# OpenHPI_Embedded_Smart_Home_RPi_Board2.net
KiCad netlist of a schematic drawn in EAGLE
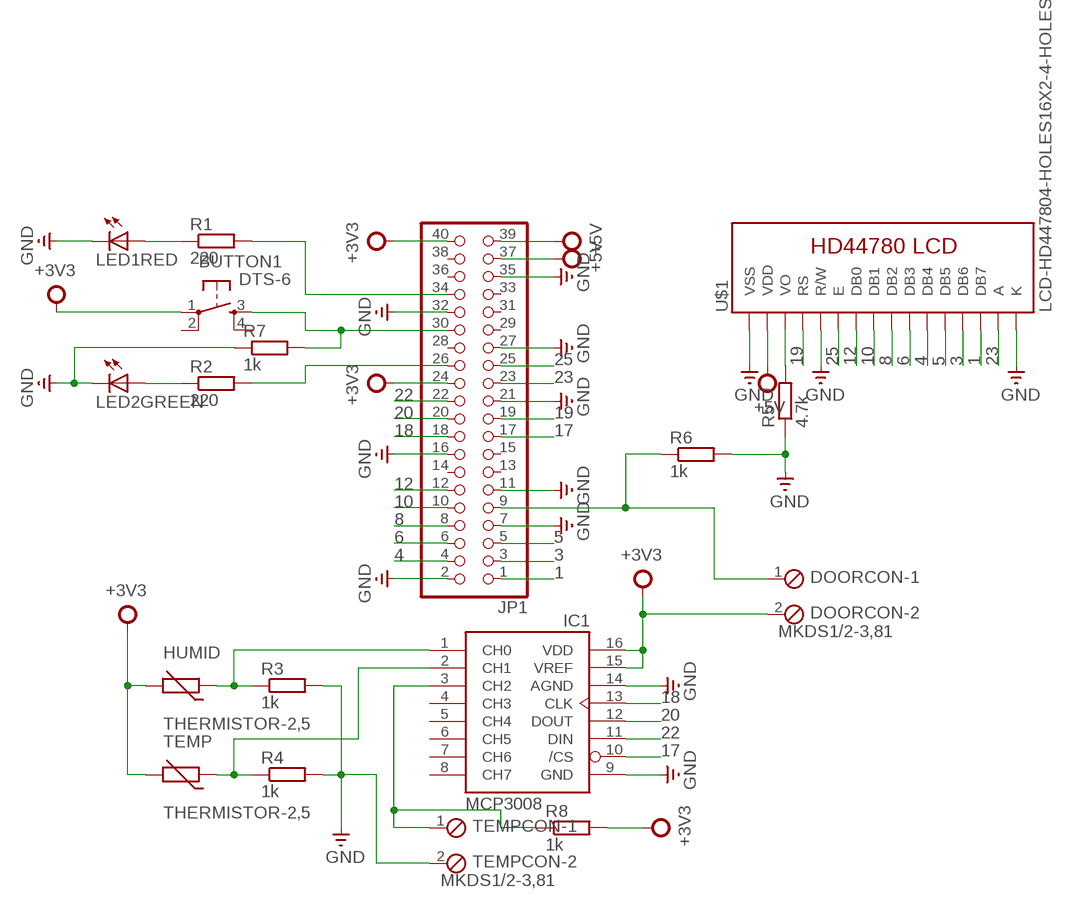
[diagram p0: schematic, sheet 1]

(export (version "E")
  (design (tool "Eeschema 10.0.6"))
  (components
    (comp (ref "BUTTON1")
      (value "DTS-6")
      (footprint "eagle-import:DTS-6")
      (libsource (lib "eagle-import") (part "DTS-6"))
    )
    (comp (ref "DOORCON")
      (value "MKDS1/2-3,81")
      (footprint "eagle-import:2POL381")
      (libsource (lib "eagle-import") (part "MKDS1/2-3,81"))
    )
    (comp (ref "HUMID")
      (value "THERMISTOR-2,5")
      (footprint "eagle-import:RS-2,5")
      (libsource (lib "eagle-import") (part "THERMISTOR-2,5"))
    )
    (comp (ref "IC1")
      (value "MCP3008")
      (footprint "eagle-import:DIL16")
      (libsource (lib "eagle-import") (part "MCP3008"))
    )
    (comp (ref "JP1")
      (value "PINHD-2X20")
      (footprint "eagle-import:2X20")
      (libsource (lib "eagle-import") (part "PINHD-2X20"))
    )
    (comp (ref "LED1RED")
      (value "LED5MM")
      (footprint "eagle-import:LED5MM")
      (libsource (lib "eagle-import") (part "LED5MM"))
    )
    (comp (ref "LED2GREEN")
      (value "LED5MM")
      (footprint "eagle-import:LED5MM")
      (libsource (lib "eagle-import") (part "LED5MM"))
    )
    (comp (ref "R1")
      (value "220")
      (footprint "eagle-import:0207_7")
      (libsource (lib "eagle-import") (part "R-EU_0207/7"))
    )
    (comp (ref "R2")
      (value "220")
      (footprint "eagle-import:0207_7")
      (libsource (lib "eagle-import") (part "R-EU_0207/7"))
    )
    (comp (ref "R3")
      (value "1k")
      (footprint "eagle-import:0207_7")
      (libsource (lib "eagle-import") (part "R-EU_0207/7"))
    )
    (comp (ref "R4")
      (value "1k")
      (footprint "eagle-import:0207_7")
      (libsource (lib "eagle-import") (part "R-EU_0207/7"))
    )
    (comp (ref "R5")
      (value "4.7k")
      (footprint "eagle-import:0207_7")
      (libsource (lib "eagle-import") (part "R-EU_0207/7"))
    )
    (comp (ref "R6")
      (value "1k")
      (footprint "eagle-import:0207_7")
      (libsource (lib "eagle-import") (part "R-EU_0207/7"))
    )
    (comp (ref "R7")
      (value "1k")
      (footprint "eagle-import:0207_7")
      (libsource (lib "eagle-import") (part "R-EU_0207/7"))
    )
    (comp (ref "R8")
      (value "1k")
      (footprint "eagle-import:0207_7")
      (libsource (lib "eagle-import") (part "R-EU_0207/7"))
    )
    (comp (ref "TEMP")
      (value "THERMISTOR-2,5")
      (footprint "eagle-import:RS-2,5")
      (libsource (lib "eagle-import") (part "THERMISTOR-2,5"))
    )
    (comp (ref "TEMPCON")
      (value "MKDS1/2-3,81")
      (footprint "eagle-import:2POL381")
      (libsource (lib "eagle-import") (part "MKDS1/2-3,81"))
    )
    (comp (ref "U$1")
      (value "LCD-HD447804-HOLES16X2-4-HOLES")
      (footprint "eagle-import:LCD-16X2-4HOLES")
      (libsource (lib "eagle-import") (part "LCD-HD4478016X2-4-HOLES4-HOLES"))
    )
  )
  (nets
    (net (code "1") (name "+3V3") (class "Default")
      (node (ref "BUTTON1") (pin "1") (pinfunction "1_1") (pintype "passive"))
      (node (ref "DOORCON") (pin "2") (pinfunction "1_2") (pintype "passive"))
      (node (ref "HUMID") (pin "2") (pinfunction "2_2") (pintype "passive"))
      (node (ref "IC1") (pin "15") (pinfunction "VREF_15") (pintype "input"))
      (node (ref "IC1") (pin "16") (pinfunction "VDD_16") (pintype "power_in"))
      (node (ref "JP1") (pin "24") (pinfunction "24_24") (pintype "passive"))
      (node (ref "JP1") (pin "40") (pinfunction "40_40") (pintype "passive"))
      (node (ref "R8") (pin "2") (pinfunction "2_2") (pintype "passive"))
      (node (ref "TEMP") (pin "2") (pinfunction "2_2") (pintype "passive"))
    )
    (net (code "2") (name "+5V") (class "Default")
      (node (ref "JP1") (pin "37") (pinfunction "37_37") (pintype "passive"))
      (node (ref "JP1") (pin "39") (pinfunction "39_39") (pintype "passive"))
      (node (ref "U$1") (pin "2") (pinfunction "VDD_2") (pintype "power_in"))
    )
    (net (code "3") (name "/1") (class "Default")
      (node (ref "JP1") (pin "1") (pinfunction "1_1") (pintype "passive"))
      (node (ref "U$1") (pin "14") (pinfunction "DB7_14") (pintype "bidirectional"))
    )
    (net (code "4") (name "/3") (class "Default")
      (node (ref "JP1") (pin "3") (pinfunction "3_3") (pintype "passive"))
      (node (ref "U$1") (pin "13") (pinfunction "DB6_13") (pintype "bidirectional"))
    )
    (net (code "5") (name "/4") (class "Default")
      (node (ref "JP1") (pin "4") (pinfunction "4_4") (pintype "passive"))
      (node (ref "U$1") (pin "11") (pinfunction "DB4_11") (pintype "bidirectional"))
    )
    (net (code "6") (name "/5") (class "Default")
      (node (ref "JP1") (pin "5") (pinfunction "5_5") (pintype "passive"))
      (node (ref "U$1") (pin "12") (pinfunction "DB5_12") (pintype "bidirectional"))
    )
    (net (code "7") (name "/6") (class "Default")
      (node (ref "JP1") (pin "6") (pinfunction "6_6") (pintype "passive"))
      (node (ref "U$1") (pin "10") (pinfunction "DB3_10") (pintype "bidirectional"))
    )
    (net (code "8") (name "/8") (class "Default")
      (node (ref "JP1") (pin "8") (pinfunction "8_8") (pintype "passive"))
      (node (ref "U$1") (pin "9") (pinfunction "DB2_9") (pintype "bidirectional"))
    )
    (net (code "9") (name "/10") (class "Default")
      (node (ref "JP1") (pin "10") (pinfunction "10_10") (pintype "passive"))
      (node (ref "U$1") (pin "8") (pinfunction "DB1_8") (pintype "bidirectional"))
    )
    (net (code "10") (name "/12") (class "Default")
      (node (ref "JP1") (pin "12") (pinfunction "12_12") (pintype "passive"))
      (node (ref "U$1") (pin "7") (pinfunction "DB0_7") (pintype "bidirectional"))
    )
    (net (code "11") (name "/17") (class "Default")
      (node (ref "IC1") (pin "10") (pinfunction "/CS_10") (pintype "input"))
      (node (ref "JP1") (pin "17") (pinfunction "17_17") (pintype "passive"))
    )
    (net (code "12") (name "/18") (class "Default")
      (node (ref "IC1") (pin "13") (pinfunction "CLK_13") (pintype "input"))
      (node (ref "JP1") (pin "18") (pinfunction "18_18") (pintype "passive"))
    )
    (net (code "13") (name "/19") (class "Default")
      (node (ref "JP1") (pin "19") (pinfunction "19_19") (pintype "passive"))
      (node (ref "U$1") (pin "4") (pinfunction "RS_4") (pintype "input"))
    )
    (net (code "14") (name "/20") (class "Default")
      (node (ref "IC1") (pin "12") (pinfunction "DOUT_12") (pintype "output"))
      (node (ref "JP1") (pin "20") (pinfunction "20_20") (pintype "passive"))
    )
    (net (code "15") (name "/22") (class "Default")
      (node (ref "IC1") (pin "11") (pinfunction "DIN_11") (pintype "input"))
      (node (ref "JP1") (pin "22") (pinfunction "22_22") (pintype "passive"))
    )
    (net (code "16") (name "/23") (class "Default")
      (node (ref "JP1") (pin "23") (pinfunction "23_23") (pintype "passive"))
      (node (ref "U$1") (pin "15") (pinfunction "A_15") (pintype "power_in"))
    )
    (net (code "17") (name "/25") (class "Default")
      (node (ref "JP1") (pin "25") (pinfunction "25_25") (pintype "passive"))
      (node (ref "U$1") (pin "6") (pinfunction "E_6") (pintype "input"))
    )
    (net (code "18") (name "GND") (class "Default")
      (node (ref "IC1") (pin "14") (pinfunction "AGND_14") (pintype "power_in"))
      (node (ref "IC1") (pin "9") (pinfunction "GND_9") (pintype "power_in"))
      (node (ref "JP1") (pin "11") (pinfunction "11_11") (pintype "passive"))
      (node (ref "JP1") (pin "16") (pinfunction "16_16") (pintype "passive"))
      (node (ref "JP1") (pin "2") (pinfunction "2_2") (pintype "passive"))
      (node (ref "JP1") (pin "21") (pinfunction "21_21") (pintype "passive"))
      (node (ref "JP1") (pin "27") (pinfunction "27_27") (pintype "passive"))
      (node (ref "JP1") (pin "32") (pinfunction "32_32") (pintype "passive"))
      (node (ref "JP1") (pin "35") (pinfunction "35_35") (pintype "passive"))
      (node (ref "JP1") (pin "7") (pinfunction "7_7") (pintype "passive"))
      (node (ref "LED1RED") (pin "K") (pinfunction "C_K") (pintype "passive"))
      (node (ref "LED2GREEN") (pin "K") (pinfunction "C_K") (pintype "passive"))
      (node (ref "R3") (pin "2") (pinfunction "2_2") (pintype "passive"))
      (node (ref "R4") (pin "2") (pinfunction "2_2") (pintype "passive"))
      (node (ref "R5") (pin "1") (pinfunction "1_1") (pintype "passive"))
      (node (ref "R6") (pin "2") (pinfunction "2_2") (pintype "passive"))
      (node (ref "R7") (pin "1") (pinfunction "1_1") (pintype "passive"))
      (node (ref "TEMPCON") (pin "2") (pinfunction "1_2") (pintype "passive"))
      (node (ref "U$1") (pin "1") (pinfunction "VSS_1") (pintype "power_in"))
      (node (ref "U$1") (pin "16") (pinfunction "K_16") (pintype "power_in"))
      (node (ref "U$1") (pin "5") (pinfunction "R/W_5") (pintype "input"))
    )
    (net (code "19") (name "Net-(BUTTON1-Pad3)") (class "Default")
      (node (ref "BUTTON1") (pin "3") (pinfunction "3_3") (pintype "passive"))
      (node (ref "JP1") (pin "30") (pinfunction "30_30") (pintype "passive"))
      (node (ref "R7") (pin "2") (pinfunction "2_2") (pintype "passive"))
    )
    (net (code "20") (name "Net-(DOORCON-Pad1)") (class "Default")
      (node (ref "DOORCON") (pin "1") (pinfunction "1_1") (pintype "passive"))
      (node (ref "JP1") (pin "9") (pinfunction "9_9") (pintype "passive"))
      (node (ref "R6") (pin "1") (pinfunction "1_1") (pintype "passive"))
    )
    (net (code "21") (name "Net-(IC1-CH0)") (class "Default")
      (node (ref "HUMID") (pin "1") (pinfunction "1_1") (pintype "passive"))
      (node (ref "IC1") (pin "1") (pinfunction "CH0_1") (pintype "input"))
      (node (ref "R3") (pin "1") (pinfunction "1_1") (pintype "passive"))
    )
    (net (code "22") (name "Net-(IC1-CH1)") (class "Default")
      (node (ref "IC1") (pin "2") (pinfunction "CH1_2") (pintype "input"))
      (node (ref "R4") (pin "1") (pinfunction "1_1") (pintype "passive"))
      (node (ref "TEMP") (pin "1") (pinfunction "1_1") (pintype "passive"))
    )
    (net (code "23") (name "Net-(IC1-CH2)") (class "Default")
      (node (ref "IC1") (pin "3") (pinfunction "CH2_3") (pintype "input"))
      (node (ref "R8") (pin "1") (pinfunction "1_1") (pintype "passive"))
      (node (ref "TEMPCON") (pin "1") (pinfunction "1_1") (pintype "passive"))
    )
    (net (code "24") (name "Net-(JP1-Pad26)") (class "Default")
      (node (ref "JP1") (pin "26") (pinfunction "26_26") (pintype "passive"))
      (node (ref "R2") (pin "2") (pinfunction "2_2") (pintype "passive"))
    )
    (net (code "25") (name "Net-(JP1-Pad34)") (class "Default")
      (node (ref "JP1") (pin "34") (pinfunction "34_34") (pintype "passive"))
      (node (ref "R1") (pin "2") (pinfunction "2_2") (pintype "passive"))
    )
    (net (code "26") (name "Net-(LED1RED-PadA)") (class "Default")
      (node (ref "LED1RED") (pin "A") (pinfunction "A_A") (pintype "passive"))
      (node (ref "R1") (pin "1") (pinfunction "1_1") (pintype "passive"))
    )
    (net (code "27") (name "Net-(LED2GREEN-PadA)") (class "Default")
      (node (ref "LED2GREEN") (pin "A") (pinfunction "A_A") (pintype "passive"))
      (node (ref "R2") (pin "1") (pinfunction "1_1") (pintype "passive"))
    )
    (net (code "28") (name "Net-(U$1-VO)") (class "Default")
      (node (ref "R5") (pin "2") (pinfunction "2_2") (pintype "passive"))
      (node (ref "U$1") (pin "3") (pinfunction "VO_3") (pintype "bidirectional"))
    )
    (net (code "29") (name "unconnected-(BUTTON1-Pad2)") (class "Default")
      (node (ref "BUTTON1") (pin "2") (pinfunction "2_2") (pintype "passive"))
    )
    (net (code "30") (name "unconnected-(BUTTON1-Pad4)") (class "Default")
      (node (ref "BUTTON1") (pin "4") (pinfunction "4_4") (pintype "passive"))
    )
    (net (code "31") (name "unconnected-(IC1-CH3-Pad4)") (class "Default")
      (node (ref "IC1") (pin "4") (pinfunction "CH3_4") (pintype "input"))
    )
    (net (code "32") (name "unconnected-(IC1-CH4-Pad5)") (class "Default")
      (node (ref "IC1") (pin "5") (pinfunction "CH4_5") (pintype "input"))
    )
    (net (code "33") (name "unconnected-(IC1-CH5-Pad6)") (class "Default")
      (node (ref "IC1") (pin "6") (pinfunction "CH5_6") (pintype "input"))
    )
    (net (code "34") (name "unconnected-(IC1-CH6-Pad7)") (class "Default")
      (node (ref "IC1") (pin "7") (pinfunction "CH6_7") (pintype "input"))
    )
    (net (code "35") (name "unconnected-(IC1-CH7-Pad8)") (class "Default")
      (node (ref "IC1") (pin "8") (pinfunction "CH7_8") (pintype "input"))
    )
    (net (code "36") (name "unconnected-(JP1-Pad13)") (class "Default")
      (node (ref "JP1") (pin "13") (pinfunction "13_13") (pintype "passive"))
    )
    (net (code "37") (name "unconnected-(JP1-Pad14)") (class "Default")
      (node (ref "JP1") (pin "14") (pinfunction "14_14") (pintype "passive"))
    )
    (net (code "38") (name "unconnected-(JP1-Pad15)") (class "Default")
      (node (ref "JP1") (pin "15") (pinfunction "15_15") (pintype "passive"))
    )
    (net (code "39") (name "unconnected-(JP1-Pad28)") (class "Default")
      (node (ref "JP1") (pin "28") (pinfunction "28_28") (pintype "passive"))
    )
    (net (code "40") (name "unconnected-(JP1-Pad29)") (class "Default")
      (node (ref "JP1") (pin "29") (pinfunction "29_29") (pintype "passive"))
    )
    (net (code "41") (name "unconnected-(JP1-Pad31)") (class "Default")
      (node (ref "JP1") (pin "31") (pinfunction "31_31") (pintype "passive"))
    )
    (net (code "42") (name "unconnected-(JP1-Pad33)") (class "Default")
      (node (ref "JP1") (pin "33") (pinfunction "33_33") (pintype "passive"))
    )
    (net (code "43") (name "unconnected-(JP1-Pad36)") (class "Default")
      (node (ref "JP1") (pin "36") (pinfunction "36_36") (pintype "passive"))
    )
    (net (code "44") (name "unconnected-(JP1-Pad38)") (class "Default")
      (node (ref "JP1") (pin "38") (pinfunction "38_38") (pintype "passive"))
    )
  )
)
